# AG1170_Breakout.net
KiCad netlist of a schematic drawn in EAGLE
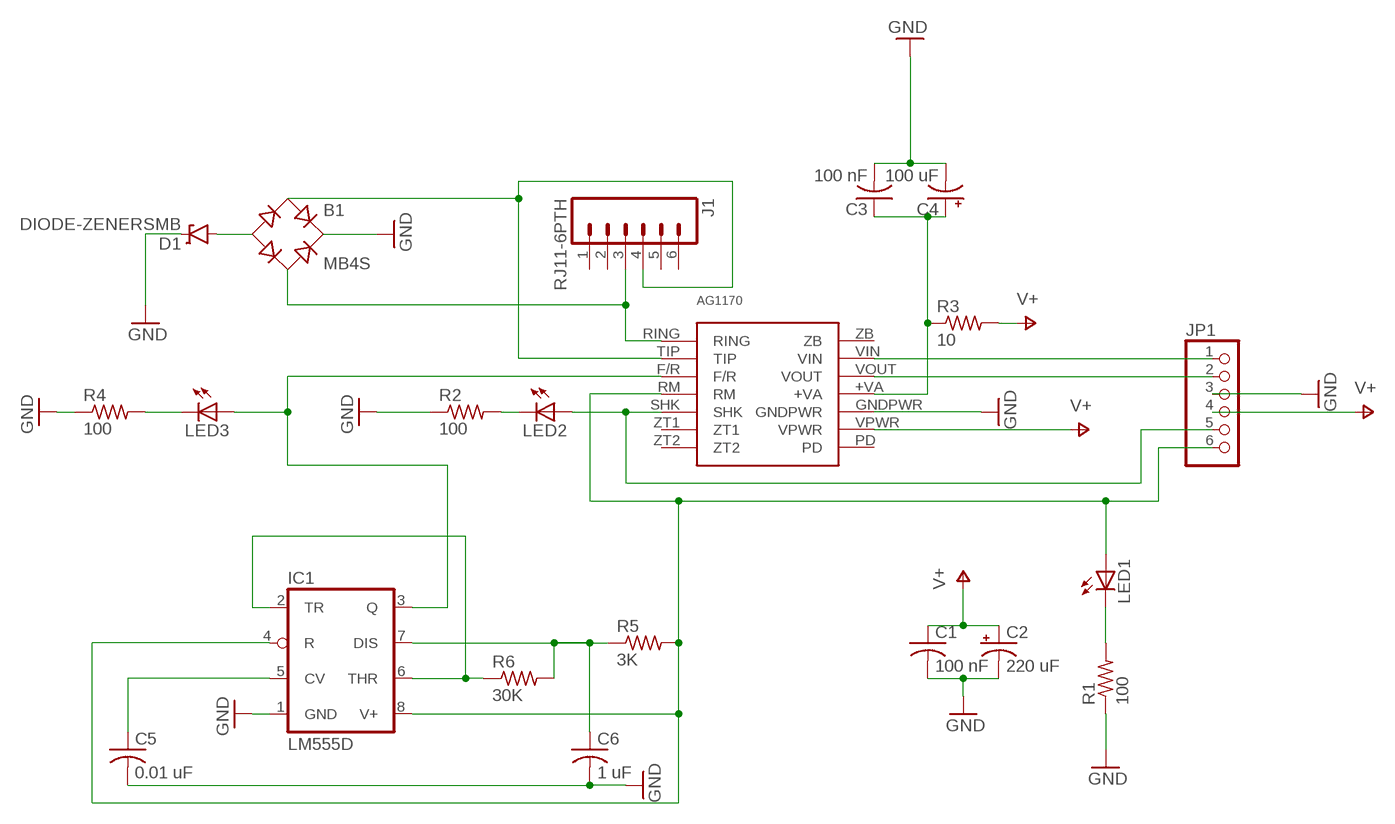
[diagram p0: schematic, sheet 1]

(export (version "E")
  (design (tool "Eeschema 10.0.6"))
  (components
    (comp (ref "AG1170")
      (value "AG1170")
      (footprint "eagle-import:AG1170")
      (libsource (lib "eagle-import") (part "AG1170"))
    )
    (comp (ref "B1")
      (value "MB4S")
      (footprint "eagle-import:SOIC-4")
      (libsource (lib "eagle-import") (part "MBS4"))
    )
    (comp (ref "C1")
      (value "100 nF")
      (footprint "eagle-import:C0805")
      (libsource (lib "eagle-import") (part "C-USC0805"))
    )
    (comp (ref "C2")
      (value "220 uF")
      (footprint "eagle-import:EIA3216")
      (libsource (lib "eagle-import") (part "CAP_POL1206"))
    )
    (comp (ref "C3")
      (value "100 nF")
      (footprint "eagle-import:C0805")
      (libsource (lib "eagle-import") (part "C-USC0805"))
    )
    (comp (ref "C4")
      (value "100 uF")
      (footprint "eagle-import:EIA3216")
      (libsource (lib "eagle-import") (part "CAP_POL1206"))
    )
    (comp (ref "C5")
      (value "0.01 uF")
      (footprint "eagle-import:C0805")
      (libsource (lib "eagle-import") (part "C-USC0805"))
    )
    (comp (ref "C6")
      (value "1 uF")
      (footprint "eagle-import:C0805")
      (libsource (lib "eagle-import") (part "C-USC0805"))
    )
    (comp (ref "D1")
      (value "DIODE-ZENERSMB")
      (footprint "eagle-import:SMB-DIODE")
      (libsource (lib "eagle-import") (part "DIODE-ZENERSMB"))
    )
    (comp (ref "IC1")
      (value "LM555D")
      (footprint "eagle-import:SO08")
      (libsource (lib "eagle-import") (part "555DLM"))
    )
    (comp (ref "J1")
      (value "RJ11-6PTH")
      (footprint "eagle-import:RJ11-6")
      (libsource (lib "eagle-import") (part "RJ11-6PTH"))
    )
    (comp (ref "JP1")
      (value "PINHD-1X6")
      (footprint "eagle-import:1X06")
      (libsource (lib "eagle-import") (part "PINHD-1X6"))
    )
    (comp (ref "LED1")
      (value "LEDCHIP-LED0805")
      (footprint "eagle-import:CHIP-LED0805")
      (libsource (lib "eagle-import") (part "LEDCHIP-LED0805"))
    )
    (comp (ref "LED2")
      (value "LEDCHIP-LED0805")
      (footprint "eagle-import:CHIP-LED0805")
      (libsource (lib "eagle-import") (part "LEDCHIP-LED0805"))
    )
    (comp (ref "LED3")
      (value "LEDCHIP-LED0805")
      (footprint "eagle-import:CHIP-LED0805")
      (libsource (lib "eagle-import") (part "LEDCHIP-LED0805"))
    )
    (comp (ref "R1")
      (value "100")
      (footprint "eagle-import:R0805")
      (libsource (lib "eagle-import") (part "R-US_R0805"))
    )
    (comp (ref "R2")
      (value "100")
      (footprint "eagle-import:R0805")
      (libsource (lib "eagle-import") (part "R-US_R0805"))
    )
    (comp (ref "R3")
      (value "10")
      (footprint "eagle-import:R0805")
      (libsource (lib "eagle-import") (part "R-US_R0805"))
    )
    (comp (ref "R4")
      (value "100")
      (footprint "eagle-import:R0805")
      (libsource (lib "eagle-import") (part "R-US_R0805"))
    )
    (comp (ref "R5")
      (value "3K")
      (footprint "eagle-import:R0805")
      (libsource (lib "eagle-import") (part "R-US_R0805"))
    )
    (comp (ref "R6")
      (value "30K")
      (footprint "eagle-import:R0805")
      (libsource (lib "eagle-import") (part "R-US_R0805"))
    )
  )
  (nets
    (net (code "1") (name "GND") (class "Default")
      (node (ref "AG1170") (pin "GNDPWR") (pinfunction "GNDPWR_GNDPWR") (pintype "power_in"))
      (node (ref "B1") (pin "+") (pinfunction "+_+") (pintype "passive"))
      (node (ref "C1") (pin "2") (pinfunction "2_2") (pintype "passive"))
      (node (ref "C2") (pin "C") (pinfunction "-_C") (pintype "passive"))
      (node (ref "C3") (pin "2") (pinfunction "2_2") (pintype "passive"))
      (node (ref "C4") (pin "C") (pinfunction "-_C") (pintype "passive"))
      (node (ref "C5") (pin "2") (pinfunction "2_2") (pintype "passive"))
      (node (ref "C6") (pin "2") (pinfunction "2_2") (pintype "passive"))
      (node (ref "D1") (pin "C") (pinfunction "C_C") (pintype "passive"))
      (node (ref "IC1") (pin "1") (pinfunction "GND_1") (pintype "power_in"))
      (node (ref "JP1") (pin "3") (pinfunction "3_3") (pintype "passive"))
      (node (ref "R1") (pin "1") (pinfunction "1_1") (pintype "passive"))
      (node (ref "R2") (pin "1") (pinfunction "1_1") (pintype "passive"))
      (node (ref "R4") (pin "1") (pinfunction "1_1") (pintype "passive"))
    )
    (net (code "2") (name "Net-(AG1170-PadSHK)") (class "Default")
      (node (ref "AG1170") (pin "SHK") (pinfunction "SHK_SHK") (pintype "output"))
      (node (ref "JP1") (pin "5") (pinfunction "5_5") (pintype "passive"))
      (node (ref "LED2") (pin "A") (pinfunction "A_A") (pintype "passive"))
    )
    (net (code "3") (name "Net-(AG1170-PadVIN)") (class "Default")
      (node (ref "AG1170") (pin "VIN") (pinfunction "VIN_VIN") (pintype "bidirectional"))
      (node (ref "JP1") (pin "1") (pinfunction "1_1") (pintype "passive"))
    )
    (net (code "4") (name "Net-(AG1170-PadVOUT)") (class "Default")
      (node (ref "AG1170") (pin "VOUT") (pinfunction "VOUT_VOUT") (pintype "bidirectional"))
      (node (ref "JP1") (pin "2") (pinfunction "2_2") (pintype "passive"))
    )
    (net (code "5") (name "Net-(B1-AC1)") (class "Default")
      (node (ref "AG1170") (pin "TIP") (pinfunction "TIP_TIP") (pintype "bidirectional"))
      (node (ref "B1") (pin "~1") (pinfunction "AC1_~1") (pintype "passive"))
      (node (ref "J1") (pin "4") (pinfunction "4_4") (pintype "passive"))
    )
    (net (code "6") (name "Net-(B1-AC2)") (class "Default")
      (node (ref "AG1170") (pin "RING") (pinfunction "RING_RING") (pintype "bidirectional"))
      (node (ref "B1") (pin "~2") (pinfunction "AC2_~2") (pintype "passive"))
      (node (ref "J1") (pin "3") (pinfunction "3_3") (pintype "passive"))
    )
    (net (code "7") (name "Net-(B1-Pad-)") (class "Default")
      (node (ref "B1") (pin "-") (pinfunction "-_-") (pintype "passive"))
      (node (ref "D1") (pin "A") (pinfunction "A_A") (pintype "passive"))
    )
    (net (code "8") (name "Net-(C4-+)") (class "Default")
      (node (ref "AG1170") (pin "+VA") (pinfunction "+VA_+VA") (pintype "power_in"))
      (node (ref "C3") (pin "1") (pinfunction "1_1") (pintype "passive"))
      (node (ref "C4") (pin "A") (pinfunction "+_A") (pintype "passive"))
      (node (ref "R3") (pin "1") (pinfunction "1_1") (pintype "passive"))
    )
    (net (code "9") (name "Net-(IC1-CV)") (class "Default")
      (node (ref "C5") (pin "1") (pinfunction "1_1") (pintype "passive"))
      (node (ref "IC1") (pin "5") (pinfunction "CV_5") (pintype "input"))
    )
    (net (code "10") (name "Net-(IC1-DIS)") (class "Default")
      (node (ref "C6") (pin "1") (pinfunction "1_1") (pintype "passive"))
      (node (ref "IC1") (pin "7") (pinfunction "DIS_7") (pintype "input"))
      (node (ref "R5") (pin "1") (pinfunction "1_1") (pintype "passive"))
      (node (ref "R6") (pin "2") (pinfunction "2_2") (pintype "passive"))
    )
    (net (code "11") (name "Net-(IC1-Q)") (class "Default")
      (node (ref "AG1170") (pin "F/R") (pinfunction "F/R_F/R") (pintype "input"))
      (node (ref "IC1") (pin "3") (pinfunction "Q_3") (pintype "output"))
      (node (ref "LED3") (pin "A") (pinfunction "A_A") (pintype "passive"))
    )
    (net (code "12") (name "Net-(IC1-R)") (class "Default")
      (node (ref "AG1170") (pin "RM") (pinfunction "RM_RM") (pintype "input"))
      (node (ref "IC1") (pin "4") (pinfunction "R_4") (pintype "input"))
      (node (ref "IC1") (pin "8") (pinfunction "V+_8") (pintype "power_in"))
      (node (ref "JP1") (pin "6") (pinfunction "6_6") (pintype "passive"))
      (node (ref "LED1") (pin "A") (pinfunction "A_A") (pintype "passive"))
      (node (ref "R5") (pin "2") (pinfunction "2_2") (pintype "passive"))
    )
    (net (code "13") (name "Net-(IC1-THR)") (class "Default")
      (node (ref "IC1") (pin "2") (pinfunction "TR_2") (pintype "input"))
      (node (ref "IC1") (pin "6") (pinfunction "THR_6") (pintype "input"))
      (node (ref "R6") (pin "1") (pinfunction "1_1") (pintype "passive"))
    )
    (net (code "14") (name "Net-(LED1-PadC)") (class "Default")
      (node (ref "LED1") (pin "C") (pinfunction "C_C") (pintype "passive"))
      (node (ref "R1") (pin "2") (pinfunction "2_2") (pintype "passive"))
    )
    (net (code "15") (name "Net-(LED2-PadC)") (class "Default")
      (node (ref "LED2") (pin "C") (pinfunction "C_C") (pintype "passive"))
      (node (ref "R2") (pin "2") (pinfunction "2_2") (pintype "passive"))
    )
    (net (code "16") (name "Net-(LED3-PadC)") (class "Default")
      (node (ref "LED3") (pin "C") (pinfunction "C_C") (pintype "passive"))
      (node (ref "R4") (pin "2") (pinfunction "2_2") (pintype "passive"))
    )
    (net (code "17") (name "V+") (class "Default")
      (node (ref "AG1170") (pin "VPWR") (pinfunction "VPWR_VPWR") (pintype "power_in"))
      (node (ref "C1") (pin "1") (pinfunction "1_1") (pintype "passive"))
      (node (ref "C2") (pin "A") (pinfunction "+_A") (pintype "passive"))
      (node (ref "JP1") (pin "4") (pinfunction "4_4") (pintype "passive"))
      (node (ref "R3") (pin "2") (pinfunction "2_2") (pintype "passive"))
    )
    (net (code "18") (name "unconnected-(AG1170-PadPD)") (class "Default")
      (node (ref "AG1170") (pin "PD") (pinfunction "PD_PD") (pintype "input"))
    )
    (net (code "19") (name "unconnected-(AG1170-PadZB)") (class "Default")
      (node (ref "AG1170") (pin "ZB") (pinfunction "ZB_ZB") (pintype "no_connect"))
    )
    (net (code "20") (name "unconnected-(AG1170-PadZT1)") (class "Default")
      (node (ref "AG1170") (pin "ZT1") (pinfunction "ZT1_ZT1") (pintype "no_connect"))
    )
    (net (code "21") (name "unconnected-(AG1170-PadZT2)") (class "Default")
      (node (ref "AG1170") (pin "ZT2") (pinfunction "ZT2_ZT2") (pintype "no_connect"))
    )
    (net (code "22") (name "unconnected-(J1-Pad1)") (class "Default")
      (node (ref "J1") (pin "1") (pinfunction "1_1") (pintype "passive"))
    )
    (net (code "23") (name "unconnected-(J1-Pad2)") (class "Default")
      (node (ref "J1") (pin "2") (pinfunction "2_2") (pintype "passive"))
    )
    (net (code "24") (name "unconnected-(J1-Pad5)") (class "Default")
      (node (ref "J1") (pin "5") (pinfunction "5_5") (pintype "passive"))
    )
    (net (code "25") (name "unconnected-(J1-Pad6)") (class "Default")
      (node (ref "J1") (pin "6") (pinfunction "6_6") (pintype "passive"))
    )
  )
)
